# Gamebadge3_revB.net
KiCad netlist of a schematic drawn in EAGLE
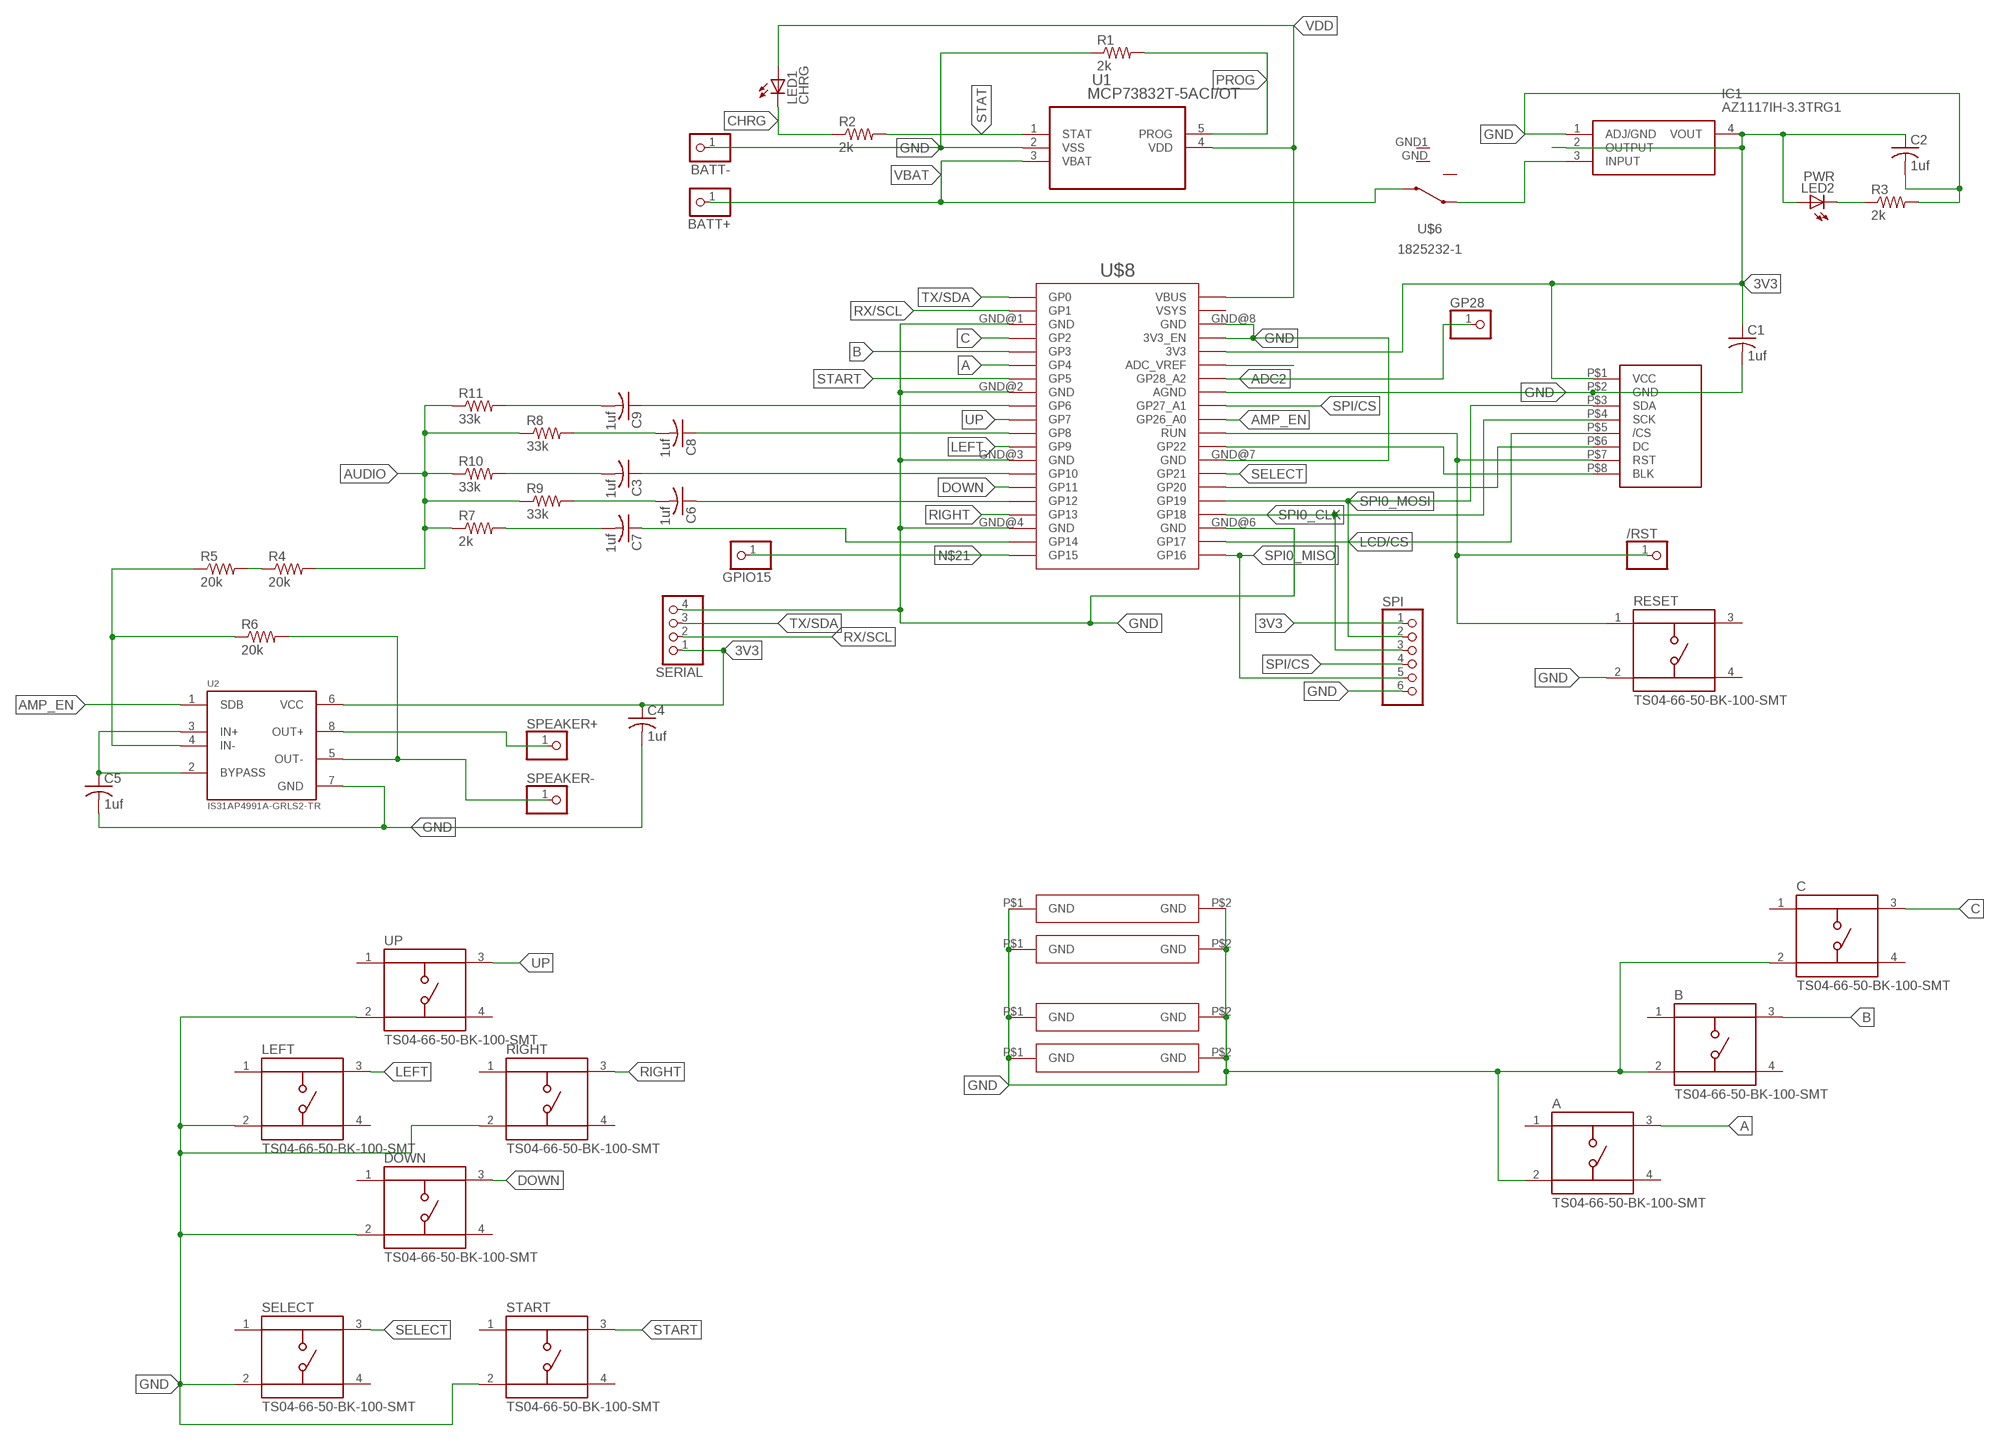
[diagram p0: schematic, sheet 1]

(export (version "E")
  (design (tool "Eeschema 10.0.6"))
  (components
    (comp (ref "/RST")
      (value "PINHD-1X1")
      (footprint "eagle-import:1X01")
      (libsource (lib "eagle-import") (part "PINHD-1X1"))
    )
    (comp (ref "A")
      (value "TS04-66-50-BK-100-SMT")
      (footprint "eagle-import:SW_TS04-66-50-BK-100-SMT")
      (fields (field (name "MF") "CUI Devices"))
      (libsource (lib "eagle-import") (part "TS04-66-50-BK-100-SMT"))
    )
    (comp (ref "B")
      (value "TS04-66-50-BK-100-SMT")
      (footprint "eagle-import:SW_TS04-66-50-BK-100-SMT")
      (fields (field (name "MF") "CUI Devices"))
      (libsource (lib "eagle-import") (part "TS04-66-50-BK-100-SMT"))
    )
    (comp (ref "BATT+")
      (value "PINHD-1X1")
      (footprint "eagle-import:1X01")
      (libsource (lib "eagle-import") (part "PINHD-1X1"))
    )
    (comp (ref "BATT-")
      (value "PINHD-1X1")
      (footprint "eagle-import:1X01")
      (libsource (lib "eagle-import") (part "PINHD-1X1"))
    )
    (comp (ref "C")
      (value "TS04-66-50-BK-100-SMT")
      (footprint "eagle-import:SW_TS04-66-50-BK-100-SMT")
      (fields (field (name "MF") "CUI Devices"))
      (libsource (lib "eagle-import") (part "TS04-66-50-BK-100-SMT"))
    )
    (comp (ref "C1")
      (value "1uf")
      (footprint "eagle-import:C0805")
      (libsource (lib "eagle-import") (part "C-USC0805"))
    )
    (comp (ref "C2")
      (value "1uf")
      (footprint "eagle-import:C0805")
      (libsource (lib "eagle-import") (part "C-USC0805"))
    )
    (comp (ref "C3")
      (value "1uf")
      (footprint "eagle-import:C0805")
      (libsource (lib "eagle-import") (part "C-USC0805"))
    )
    (comp (ref "C4")
      (value "1uf")
      (footprint "eagle-import:C0805")
      (libsource (lib "eagle-import") (part "C-USC0805"))
    )
    (comp (ref "C5")
      (value "1uf")
      (footprint "eagle-import:C0805")
      (libsource (lib "eagle-import") (part "C-USC0805"))
    )
    (comp (ref "C6")
      (value "1uf")
      (footprint "eagle-import:C0805")
      (libsource (lib "eagle-import") (part "C-USC0805"))
    )
    (comp (ref "C7")
      (value "1uf")
      (footprint "eagle-import:C0805")
      (libsource (lib "eagle-import") (part "C-USC0805"))
    )
    (comp (ref "C8")
      (value "1uf")
      (footprint "eagle-import:C0805")
      (libsource (lib "eagle-import") (part "C-USC0805"))
    )
    (comp (ref "C9")
      (value "1uf")
      (footprint "eagle-import:C0805")
      (libsource (lib "eagle-import") (part "C-USC0805"))
    )
    (comp (ref "DOWN")
      (value "TS04-66-50-BK-100-SMT")
      (footprint "eagle-import:SW_TS04-66-50-BK-100-SMT")
      (fields (field (name "MF") "CUI Devices"))
      (libsource (lib "eagle-import") (part "TS04-66-50-BK-100-SMT"))
    )
    (comp (ref "GP28")
      (value "PINHD-1X1")
      (footprint "eagle-import:1X01")
      (libsource (lib "eagle-import") (part "PINHD-1X1"))
    )
    (comp (ref "GPIO15")
      (value "PINHD-1X1")
      (footprint "eagle-import:1X01")
      (libsource (lib "eagle-import") (part "PINHD-1X1"))
    )
    (comp (ref "IC1")
      (value "AZ1117IH-3.3TRG1")
      (footprint "eagle-import:SOT230P700X170-4N")
      (fields (field (name "MF") "Diodes Inc."))
      (libsource (lib "eagle-import") (part "AZ1117IH-3.3TRG1"))
    )
    (comp (ref "LED1")
      (value "CHRG")
      (footprint "eagle-import:LED3MM")
      (libsource (lib "eagle-import") (part "LED3MM"))
    )
    (comp (ref "LED2")
      (value "PWR")
      (footprint "eagle-import:LED3MM")
      (libsource (lib "eagle-import") (part "LED3MM"))
    )
    (comp (ref "LEFT")
      (value "TS04-66-50-BK-100-SMT")
      (footprint "eagle-import:SW_TS04-66-50-BK-100-SMT")
      (fields (field (name "MF") "CUI Devices"))
      (libsource (lib "eagle-import") (part "TS04-66-50-BK-100-SMT"))
    )
    (comp (ref "R1")
      (value "2k")
      (footprint "eagle-import:R0805")
      (libsource (lib "eagle-import") (part "R-US_R0805"))
    )
    (comp (ref "R2")
      (value "2k")
      (footprint "eagle-import:R0805")
      (libsource (lib "eagle-import") (part "R-US_R0805"))
    )
    (comp (ref "R3")
      (value "2k")
      (footprint "eagle-import:R0805")
      (libsource (lib "eagle-import") (part "R-US_R0805"))
    )
    (comp (ref "R4")
      (value "20k")
      (footprint "eagle-import:R0805")
      (libsource (lib "eagle-import") (part "R-US_R0805"))
    )
    (comp (ref "R5")
      (value "20k")
      (footprint "eagle-import:R0805")
      (libsource (lib "eagle-import") (part "R-US_R0805"))
    )
    (comp (ref "R6")
      (value "20k")
      (footprint "eagle-import:R0805")
      (libsource (lib "eagle-import") (part "R-US_R0805"))
    )
    (comp (ref "R7")
      (value "2k")
      (footprint "eagle-import:R0805")
      (libsource (lib "eagle-import") (part "R-US_R0805"))
    )
    (comp (ref "R8")
      (value "33k")
      (footprint "eagle-import:R0805")
      (libsource (lib "eagle-import") (part "R-US_R0805"))
    )
    (comp (ref "R9")
      (value "33k")
      (footprint "eagle-import:R0805")
      (libsource (lib "eagle-import") (part "R-US_R0805"))
    )
    (comp (ref "R10")
      (value "33k")
      (footprint "eagle-import:R0805")
      (libsource (lib "eagle-import") (part "R-US_R0805"))
    )
    (comp (ref "R11")
      (value "33k")
      (footprint "eagle-import:R0805")
      (libsource (lib "eagle-import") (part "R-US_R0805"))
    )
    (comp (ref "RESET")
      (value "TS04-66-50-BK-100-SMT")
      (footprint "eagle-import:SW_TS04-66-50-BK-100-SMT")
      (fields (field (name "MF") "CUI Devices"))
      (libsource (lib "eagle-import") (part "TS04-66-50-BK-100-SMT"))
    )
    (comp (ref "RIGHT")
      (value "TS04-66-50-BK-100-SMT")
      (footprint "eagle-import:SW_TS04-66-50-BK-100-SMT")
      (fields (field (name "MF") "CUI Devices"))
      (libsource (lib "eagle-import") (part "TS04-66-50-BK-100-SMT"))
    )
    (comp (ref "SELECT")
      (value "TS04-66-50-BK-100-SMT")
      (footprint "eagle-import:SW_TS04-66-50-BK-100-SMT")
      (fields (field (name "MF") "CUI Devices"))
      (libsource (lib "eagle-import") (part "TS04-66-50-BK-100-SMT"))
    )
    (comp (ref "SERIAL")
      (value "PINHD-1X4")
      (footprint "eagle-import:1X04")
      (libsource (lib "eagle-import") (part "PINHD-1X4"))
    )
    (comp (ref "SPEAKER+")
      (value "PINHD-1X1")
      (footprint "eagle-import:1X01")
      (libsource (lib "eagle-import") (part "PINHD-1X1"))
    )
    (comp (ref "SPEAKER-")
      (value "PINHD-1X1")
      (footprint "eagle-import:1X01")
      (libsource (lib "eagle-import") (part "PINHD-1X1"))
    )
    (comp (ref "SPI")
      (value "PINHD-1X6")
      (footprint "eagle-import:1X06")
      (libsource (lib "eagle-import") (part "PINHD-1X6"))
    )
    (comp (ref "START")
      (value "TS04-66-50-BK-100-SMT")
      (footprint "eagle-import:SW_TS04-66-50-BK-100-SMT")
      (fields (field (name "MF") "CUI Devices"))
      (libsource (lib "eagle-import") (part "TS04-66-50-BK-100-SMT"))
    )
    (comp (ref "U$2")
      (value "GND_CLIP")
      (footprint "eagle-import:GND_CLIP")
      (libsource (lib "eagle-import") (part "GND_CLIP"))
    )
    (comp (ref "U$3")
      (value "GND_CLIP")
      (footprint "eagle-import:GND_CLIP")
      (libsource (lib "eagle-import") (part "GND_CLIP"))
    )
    (comp (ref "U$4")
      (value "GND_CLIP")
      (footprint "eagle-import:GND_CLIP")
      (libsource (lib "eagle-import") (part "GND_CLIP"))
    )
    (comp (ref "U$5")
      (value "GND_CLIP")
      (footprint "eagle-import:GND_CLIP")
      (libsource (lib "eagle-import") (part "GND_CLIP"))
    )
    (comp (ref "U$6")
      (value "1825232-1")
      (footprint "eagle-import:1825232-1")
      (fields (field (name "MF") "TE Connectivity"))
      (libsource (lib "eagle-import") (part "1825232-1"))
    )
    (comp (ref "U$7")
      (value "ST7789_CS")
      (footprint "eagle-import:ST7789_WAVE")
      (libsource (lib "eagle-import") (part "ST7789_CS"))
    )
    (comp (ref "U$8")
      (value "RPI_PICO_W")
      (footprint "eagle-import:RPI_PICO_W")
      (libsource (lib "eagle-import") (part "RPI_PICO_W"))
    )
    (comp (ref "U1")
      (value "MCP73832T-5ACI/OT")
      (footprint "eagle-import:SOT95P300X145-5N")
      (fields (field (name "MF") "Microchip"))
      (libsource (lib "eagle-import") (part "MCP73832T-5ACI/OT"))
    )
    (comp (ref "U2")
      (value "IS31AP4991A-GRLS2-TR")
      (footprint "eagle-import:SOIC127P604X170-8N")
      (fields (field (name "MF") "Lumissil Microsystems"))
      (libsource (lib "eagle-import") (part "IS31AP4991A-GRLS2-TR"))
    )
    (comp (ref "UP")
      (value "TS04-66-50-BK-100-SMT")
      (footprint "eagle-import:SW_TS04-66-50-BK-100-SMT")
      (fields (field (name "MF") "CUI Devices"))
      (libsource (lib "eagle-import") (part "TS04-66-50-BK-100-SMT"))
    )
  )
  (nets
    (net (code "1") (name "3V3") (class "Default")
      (node (ref "C1") (pin "1") (pinfunction "1_1") (pintype "passive"))
      (node (ref "C2") (pin "1") (pinfunction "1_1") (pintype "passive"))
      (node (ref "C4") (pin "1") (pinfunction "1_1") (pintype "passive"))
      (node (ref "IC1") (pin "2") (pinfunction "OUTPUT_2") (pintype "bidirectional"))
      (node (ref "IC1") (pin "4") (pinfunction "VOUT_4") (pintype "bidirectional"))
      (node (ref "LED2") (pin "A") (pinfunction "A_A") (pintype "passive"))
      (node (ref "SERIAL") (pin "1") (pinfunction "1_1") (pintype "passive"))
      (node (ref "SPI") (pin "1") (pinfunction "1_1") (pintype "passive"))
      (node (ref "U$7") (pin "P$1") (pinfunction "VCC_P$1") (pintype "bidirectional"))
      (node (ref "U$8") (pin "3V3") (pinfunction "3V3_3V3") (pintype "bidirectional"))
      (node (ref "U2") (pin "6") (pinfunction "VCC_6") (pintype "power_in"))
    )
    (net (code "2") (name "A") (class "Default")
      (node (ref "A") (pin "3") (pinfunction "3_3") (pintype "passive"))
      (node (ref "U$8") (pin "GP4") (pinfunction "GP4_GP4") (pintype "bidirectional"))
    )
    (net (code "3") (name "ADC2") (class "Default")
      (node (ref "GP28") (pin "1") (pinfunction "1_1") (pintype "passive"))
      (node (ref "U$8") (pin "GP28_A2") (pinfunction "GP28_A2_GP28_A2") (pintype "bidirectional"))
    )
    (net (code "4") (name "AMP_EN") (class "Default")
      (node (ref "U$8") (pin "GP26_A0") (pinfunction "GP26_A0_GP26_A0") (pintype "bidirectional"))
      (node (ref "U2") (pin "1") (pinfunction "SDB_1") (pintype "input"))
    )
    (net (code "5") (name "AUDIO") (class "Default")
      (node (ref "R10") (pin "1") (pinfunction "1_1") (pintype "passive"))
      (node (ref "R11") (pin "1") (pinfunction "1_1") (pintype "passive"))
      (node (ref "R4") (pin "2") (pinfunction "2_2") (pintype "passive"))
      (node (ref "R7") (pin "1") (pinfunction "1_1") (pintype "passive"))
      (node (ref "R8") (pin "1") (pinfunction "1_1") (pintype "passive"))
      (node (ref "R9") (pin "1") (pinfunction "1_1") (pintype "passive"))
    )
    (net (code "6") (name "B") (class "Default")
      (node (ref "B") (pin "3") (pinfunction "3_3") (pintype "passive"))
      (node (ref "U$8") (pin "GP3") (pinfunction "GP3_GP3") (pintype "bidirectional"))
    )
    (net (code "7") (name "C") (class "Default")
      (node (ref "C") (pin "3") (pinfunction "3_3") (pintype "passive"))
      (node (ref "U$8") (pin "GP2") (pinfunction "GP2_GP2") (pintype "bidirectional"))
    )
    (net (code "8") (name "CHRG") (class "Default")
      (node (ref "LED1") (pin "K") (pinfunction "C_K") (pintype "passive"))
      (node (ref "R2") (pin "1") (pinfunction "1_1") (pintype "passive"))
    )
    (net (code "9") (name "DOWN") (class "Default")
      (node (ref "DOWN") (pin "3") (pinfunction "3_3") (pintype "passive"))
      (node (ref "U$8") (pin "GP11") (pinfunction "GP11_GP11") (pintype "bidirectional"))
    )
    (net (code "10") (name "GND") (class "Default")
      (node (ref "A") (pin "2") (pinfunction "2_2") (pintype "passive"))
      (node (ref "B") (pin "2") (pinfunction "2_2") (pintype "passive"))
      (node (ref "BATT-") (pin "1") (pinfunction "1_1") (pintype "passive"))
      (node (ref "C") (pin "2") (pinfunction "2_2") (pintype "passive"))
      (node (ref "C1") (pin "2") (pinfunction "2_2") (pintype "passive"))
      (node (ref "C2") (pin "2") (pinfunction "2_2") (pintype "passive"))
      (node (ref "C4") (pin "2") (pinfunction "2_2") (pintype "passive"))
      (node (ref "C5") (pin "2") (pinfunction "2_2") (pintype "passive"))
      (node (ref "DOWN") (pin "2") (pinfunction "2_2") (pintype "passive"))
      (node (ref "IC1") (pin "1") (pinfunction "ADJ/GND_1") (pintype "bidirectional"))
      (node (ref "LEFT") (pin "2") (pinfunction "2_2") (pintype "passive"))
      (node (ref "R1") (pin "1") (pinfunction "1_1") (pintype "passive"))
      (node (ref "R3") (pin "2") (pinfunction "2_2") (pintype "passive"))
      (node (ref "RESET") (pin "2") (pinfunction "2_2") (pintype "passive"))
      (node (ref "RIGHT") (pin "2") (pinfunction "2_2") (pintype "passive"))
      (node (ref "SELECT") (pin "2") (pinfunction "2_2") (pintype "passive"))
      (node (ref "SERIAL") (pin "4") (pinfunction "4_4") (pintype "passive"))
      (node (ref "SPI") (pin "6") (pinfunction "6_6") (pintype "passive"))
      (node (ref "START") (pin "2") (pinfunction "2_2") (pintype "passive"))
      (node (ref "U$2") (pin "P$1") (pinfunction "GND_P$1") (pintype "bidirectional"))
      (node (ref "U$2") (pin "P$2") (pinfunction "GND_P$2") (pintype "bidirectional"))
      (node (ref "U$3") (pin "P$1") (pinfunction "GND_P$1") (pintype "bidirectional"))
      (node (ref "U$3") (pin "P$2") (pinfunction "GND_P$2") (pintype "bidirectional"))
      (node (ref "U$4") (pin "P$1") (pinfunction "GND_P$1") (pintype "bidirectional"))
      (node (ref "U$4") (pin "P$2") (pinfunction "GND_P$2") (pintype "bidirectional"))
      (node (ref "U$5") (pin "P$1") (pinfunction "GND_P$1") (pintype "bidirectional"))
      (node (ref "U$5") (pin "P$2") (pinfunction "GND_P$2") (pintype "bidirectional"))
      (node (ref "U$7") (pin "P$2") (pinfunction "GND_P$2") (pintype "bidirectional"))
      (node (ref "U$8") (pin "3V3_EN") (pinfunction "3V3_EN_3V3_EN") (pintype "bidirectional"))
      (node (ref "U$8") (pin "AGND") (pinfunction "AGND_AGND") (pintype "bidirectional"))
      (node (ref "U$8") (pin "GND@1") (pinfunction "GND_GND@1") (pintype "bidirectional"))
      (node (ref "U$8") (pin "GND@2") (pinfunction "GND_GND@2") (pintype "bidirectional"))
      (node (ref "U$8") (pin "GND@3") (pinfunction "GND_GND@3") (pintype "bidirectional"))
      (node (ref "U$8") (pin "GND@4") (pinfunction "GND_GND@4") (pintype "bidirectional"))
      (node (ref "U$8") (pin "GND@6") (pinfunction "GND_GND@6") (pintype "bidirectional"))
      (node (ref "U$8") (pin "GND@7") (pinfunction "GND_GND@7") (pintype "bidirectional"))
      (node (ref "U$8") (pin "GND@8") (pinfunction "GND_GND@8") (pintype "bidirectional"))
      (node (ref "U1") (pin "2") (pinfunction "VSS_2") (pintype "passive"))
      (node (ref "U2") (pin "7") (pinfunction "GND_7") (pintype "power_in"))
      (node (ref "UP") (pin "2") (pinfunction "2_2") (pintype "passive"))
    )
    (net (code "11") (name "LCD{slash}CS") (class "Default")
      (node (ref "U$7") (pin "P$5") (pinfunction "/CS_P$5") (pintype "bidirectional"))
      (node (ref "U$8") (pin "GP17") (pinfunction "GP17_GP17") (pintype "bidirectional"))
    )
    (net (code "12") (name "LEFT") (class "Default")
      (node (ref "LEFT") (pin "3") (pinfunction "3_3") (pintype "passive"))
      (node (ref "U$8") (pin "GP9") (pinfunction "GP9_GP9") (pintype "bidirectional"))
    )
    (net (code "13") (name "N$21") (class "Default")
      (node (ref "GPIO15") (pin "1") (pinfunction "1_1") (pintype "passive"))
      (node (ref "U$8") (pin "GP15") (pinfunction "GP15_GP15") (pintype "bidirectional"))
    )
    (net (code "14") (name "Net-(C3-Pad1)") (class "Default")
      (node (ref "C3") (pin "1") (pinfunction "1_1") (pintype "passive"))
      (node (ref "U$8") (pin "GP10") (pinfunction "GP10_GP10") (pintype "bidirectional"))
    )
    (net (code "15") (name "Net-(C3-Pad2)") (class "Default")
      (node (ref "C3") (pin "2") (pinfunction "2_2") (pintype "passive"))
      (node (ref "R10") (pin "2") (pinfunction "2_2") (pintype "passive"))
    )
    (net (code "16") (name "Net-(C6-Pad1)") (class "Default")
      (node (ref "C6") (pin "1") (pinfunction "1_1") (pintype "passive"))
      (node (ref "U$8") (pin "GP12") (pinfunction "GP12_GP12") (pintype "bidirectional"))
    )
    (net (code "17") (name "Net-(C6-Pad2)") (class "Default")
      (node (ref "C6") (pin "2") (pinfunction "2_2") (pintype "passive"))
      (node (ref "R9") (pin "2") (pinfunction "2_2") (pintype "passive"))
    )
    (net (code "18") (name "Net-(C7-Pad1)") (class "Default")
      (node (ref "C7") (pin "1") (pinfunction "1_1") (pintype "passive"))
      (node (ref "U$8") (pin "GP14") (pinfunction "GP14_GP14") (pintype "bidirectional"))
    )
    (net (code "19") (name "Net-(C7-Pad2)") (class "Default")
      (node (ref "C7") (pin "2") (pinfunction "2_2") (pintype "passive"))
      (node (ref "R7") (pin "2") (pinfunction "2_2") (pintype "passive"))
    )
    (net (code "20") (name "Net-(C8-Pad1)") (class "Default")
      (node (ref "C8") (pin "1") (pinfunction "1_1") (pintype "passive"))
      (node (ref "U$8") (pin "GP8") (pinfunction "GP8_GP8") (pintype "bidirectional"))
    )
    (net (code "21") (name "Net-(C8-Pad2)") (class "Default")
      (node (ref "C8") (pin "2") (pinfunction "2_2") (pintype "passive"))
      (node (ref "R8") (pin "2") (pinfunction "2_2") (pintype "passive"))
    )
    (net (code "22") (name "Net-(C9-Pad1)") (class "Default")
      (node (ref "C9") (pin "1") (pinfunction "1_1") (pintype "passive"))
      (node (ref "U$8") (pin "GP6") (pinfunction "GP6_GP6") (pintype "bidirectional"))
    )
    (net (code "23") (name "Net-(C9-Pad2)") (class "Default")
      (node (ref "C9") (pin "2") (pinfunction "2_2") (pintype "passive"))
      (node (ref "R11") (pin "2") (pinfunction "2_2") (pintype "passive"))
    )
    (net (code "24") (name "Net-(IC1-INPUT)") (class "Default")
      (node (ref "IC1") (pin "3") (pinfunction "INPUT_3") (pintype "bidirectional"))
      (node (ref "U$6") (pin "3") (pinfunction "3_3") (pintype "passive"))
    )
    (net (code "25") (name "Net-(LED2-C)") (class "Default")
      (node (ref "LED2") (pin "K") (pinfunction "C_K") (pintype "passive"))
      (node (ref "R3") (pin "1") (pinfunction "1_1") (pintype "passive"))
    )
    (net (code "26") (name "Net-(R4-Pad1)") (class "Default")
      (node (ref "R4") (pin "1") (pinfunction "1_1") (pintype "passive"))
      (node (ref "R5") (pin "2") (pinfunction "2_2") (pintype "passive"))
    )
    (net (code "27") (name "Net-(U$7-BLK)") (class "Default")
      (node (ref "U$7") (pin "P$8") (pinfunction "BLK_P$8") (pintype "bidirectional"))
      (node (ref "U$8") (pin "GP22") (pinfunction "GP22_GP22") (pintype "bidirectional"))
    )
    (net (code "28") (name "Net-(U$7-DC)") (class "Default")
      (node (ref "U$7") (pin "P$6") (pinfunction "DC_P$6") (pintype "bidirectional"))
      (node (ref "U$8") (pin "GP20") (pinfunction "GP20_GP20") (pintype "bidirectional"))
    )
    (net (code "29") (name "Net-(U$7-RST)") (class "Default")
      (node (ref "/RST") (pin "1") (pinfunction "1_1") (pintype "passive"))
      (node (ref "RESET") (pin "1") (pinfunction "1_1") (pintype "passive"))
      (node (ref "U$7") (pin "P$7") (pinfunction "RST_P$7") (pintype "bidirectional"))
      (node (ref "U$8") (pin "RUN") (pinfunction "RUN_RUN") (pintype "bidirectional"))
    )
    (net (code "30") (name "Net-(U2-BYPASS)") (class "Default")
      (node (ref "C5") (pin "1") (pinfunction "1_1") (pintype "passive"))
      (node (ref "U2") (pin "2") (pinfunction "BYPASS_2") (pintype "passive"))
      (node (ref "U2") (pin "3") (pinfunction "IN+_3") (pintype "input"))
    )
    (net (code "31") (name "Net-(U2-IN-)") (class "Default")
      (node (ref "R5") (pin "1") (pinfunction "1_1") (pintype "passive"))
      (node (ref "R6") (pin "1") (pinfunction "1_1") (pintype "passive"))
      (node (ref "U2") (pin "4") (pinfunction "IN-_4") (pintype "input"))
    )
    (net (code "32") (name "Net-(U2-OUT+)") (class "Default")
      (node (ref "SPEAKER+") (pin "1") (pinfunction "1_1") (pintype "passive"))
      (node (ref "U2") (pin "8") (pinfunction "OUT+_8") (pintype "output"))
    )
    (net (code "33") (name "Net-(U2-OUT-)") (class "Default")
      (node (ref "R6") (pin "2") (pinfunction "2_2") (pintype "passive"))
      (node (ref "SPEAKER-") (pin "1") (pinfunction "1_1") (pintype "passive"))
      (node (ref "U2") (pin "5") (pinfunction "OUT-_5") (pintype "output"))
    )
    (net (code "34") (name "PROG") (class "Default")
      (node (ref "R1") (pin "2") (pinfunction "2_2") (pintype "passive"))
      (node (ref "U1") (pin "5") (pinfunction "PROG_5") (pintype "input"))
    )
    (net (code "35") (name "RIGHT") (class "Default")
      (node (ref "RIGHT") (pin "3") (pinfunction "3_3") (pintype "passive"))
      (node (ref "U$8") (pin "GP13") (pinfunction "GP13_GP13") (pintype "bidirectional"))
    )
    (net (code "36") (name "RX{slash}SCL") (class "Default")
      (node (ref "SERIAL") (pin "2") (pinfunction "2_2") (pintype "passive"))
      (node (ref "U$8") (pin "GP1") (pinfunction "GP1_GP1") (pintype "bidirectional"))
    )
    (net (code "37") (name "SELECT") (class "Default")
      (node (ref "SELECT") (pin "3") (pinfunction "3_3") (pintype "passive"))
      (node (ref "U$8") (pin "GP21") (pinfunction "GP21_GP21") (pintype "bidirectional"))
    )
    (net (code "38") (name "SPI0_CLK") (class "Default")
      (node (ref "SPI") (pin "3") (pinfunction "3_3") (pintype "passive"))
      (node (ref "U$7") (pin "P$4") (pinfunction "SCK_P$4") (pintype "bidirectional"))
      (node (ref "U$8") (pin "GP18") (pinfunction "GP18_GP18") (pintype "bidirectional"))
    )
    (net (code "39") (name "SPI0_MISO") (class "Default")
      (node (ref "SPI") (pin "5") (pinfunction "5_5") (pintype "passive"))
      (node (ref "U$8") (pin "GP16") (pinfunction "GP16_GP16") (pintype "bidirectional"))
    )
    (net (code "40") (name "SPI0_MOSI") (class "Default")
      (node (ref "SPI") (pin "2") (pinfunction "2_2") (pintype "passive"))
      (node (ref "U$7") (pin "P$3") (pinfunction "SDA_P$3") (pintype "bidirectional"))
      (node (ref "U$8") (pin "GP19") (pinfunction "GP19_GP19") (pintype "bidirectional"))
    )
    (net (code "41") (name "SPI{slash}CS") (class "Default")
      (node (ref "SPI") (pin "4") (pinfunction "4_4") (pintype "passive"))
      (node (ref "U$8") (pin "GP27_A1") (pinfunction "GP27_A1_GP27_A1") (pintype "bidirectional"))
    )
    (net (code "42") (name "START") (class "Default")
      (node (ref "START") (pin "3") (pinfunction "3_3") (pintype "passive"))
      (node (ref "U$8") (pin "GP5") (pinfunction "GP5_GP5") (pintype "bidirectional"))
    )
    (net (code "43") (name "STAT") (class "Default")
      (node (ref "R2") (pin "2") (pinfunction "2_2") (pintype "passive"))
      (node (ref "U1") (pin "1") (pinfunction "STAT_1") (pintype "input"))
    )
    (net (code "44") (name "TX{slash}SDA") (class "Default")
      (node (ref "SERIAL") (pin "3") (pinfunction "3_3") (pintype "passive"))
      (node (ref "U$8") (pin "GP0") (pinfunction "GP0_GP0") (pintype "bidirectional"))
    )
    (net (code "45") (name "UP") (class "Default")
      (node (ref "U$8") (pin "GP7") (pinfunction "GP7_GP7") (pintype "bidirectional"))
      (node (ref "UP") (pin "3") (pinfunction "3_3") (pintype "passive"))
    )
    (net (code "46") (name "VBAT") (class "Default")
      (node (ref "BATT+") (pin "1") (pinfunction "1_1") (pintype "passive"))
      (node (ref "U$6") (pin "2") (pinfunction "2_2") (pintype "passive"))
      (node (ref "U1") (pin "3") (pinfunction "VBAT_3") (pintype "input"))
    )
    (net (code "47") (name "VDD") (class "Default")
      (node (ref "LED1") (pin "A") (pinfunction "A_A") (pintype "passive"))
      (node (ref "U$8") (pin "VBUS") (pinfunction "VBUS_VBUS") (pintype "bidirectional"))
      (node (ref "U1") (pin "4") (pinfunction "VDD_4") (pintype "power_in"))
    )
    (net (code "48") (name "unconnected-(A-Pad1)") (class "Default")
      (node (ref "A") (pin "1") (pinfunction "1_1") (pintype "passive"))
    )
    (net (code "49") (name "unconnected-(A-Pad4)") (class "Default")
      (node (ref "A") (pin "4") (pinfunction "4_4") (pintype "passive"))
    )
    (net (code "50") (name "unconnected-(B-Pad1)") (class "Default")
      (node (ref "B") (pin "1") (pinfunction "1_1") (pintype "passive"))
    )
    (net (code "51") (name "unconnected-(B-Pad4)") (class "Default")
      (node (ref "B") (pin "4") (pinfunction "4_4") (pintype "passive"))
    )
    (net (code "52") (name "unconnected-(C-Pad1)") (class "Default")
      (node (ref "C") (pin "1") (pinfunction "1_1") (pintype "passive"))
    )
    (net (code "53") (name "unconnected-(C-Pad4)") (class "Default")
      (node (ref "C") (pin "4") (pinfunction "4_4") (pintype "passive"))
    )
    (net (code "54") (name "unconnected-(DOWN-Pad1)") (class "Default")
      (node (ref "DOWN") (pin "1") (pinfunction "1_1") (pintype "passive"))
    )
    (net (code "55") (name "unconnected-(DOWN-Pad4)") (class "Default")
      (node (ref "DOWN") (pin "4") (pinfunction "4_4") (pintype "passive"))
    )
    (net (code "56") (name "unconnected-(LEFT-Pad1)") (class "Default")
      (node (ref "LEFT") (pin "1") (pinfunction "1_1") (pintype "passive"))
    )
    (net (code "57") (name "unconnected-(LEFT-Pad4)") (class "Default")
      (node (ref "LEFT") (pin "4") (pinfunction "4_4") (pintype "passive"))
    )
    (net (code "58") (name "unconnected-(RESET-Pad3)") (class "Default")
      (node (ref "RESET") (pin "3") (pinfunction "3_3") (pintype "passive"))
    )
    (net (code "59") (name "unconnected-(RESET-Pad4)") (class "Default")
      (node (ref "RESET") (pin "4") (pinfunction "4_4") (pintype "passive"))
    )
    (net (code "60") (name "unconnected-(RIGHT-Pad1)") (class "Default")
      (node (ref "RIGHT") (pin "1") (pinfunction "1_1") (pintype "passive"))
    )
    (net (code "61") (name "unconnected-(RIGHT-Pad4)") (class "Default")
      (node (ref "RIGHT") (pin "4") (pinfunction "4_4") (pintype "passive"))
    )
    (net (code "62") (name "unconnected-(SELECT-Pad1)") (class "Default")
      (node (ref "SELECT") (pin "1") (pinfunction "1_1") (pintype "passive"))
    )
    (net (code "63") (name "unconnected-(SELECT-Pad4)") (class "Default")
      (node (ref "SELECT") (pin "4") (pinfunction "4_4") (pintype "passive"))
    )
    (net (code "64") (name "unconnected-(START-Pad1)") (class "Default")
      (node (ref "START") (pin "1") (pinfunction "1_1") (pintype "passive"))
    )
    (net (code "65") (name "unconnected-(START-Pad4)") (class "Default")
      (node (ref "START") (pin "4") (pinfunction "4_4") (pintype "passive"))
    )
    (net (code "66") (name "unconnected-(U$6-Pad1)") (class "Default")
      (node (ref "U$6") (pin "1") (pinfunction "1_1") (pintype "passive"))
    )
    (net (code "67") (name "unconnected-(U$6-PadGND)") (class "Default")
      (node (ref "U$6") (pin "GND") (pinfunction "GND_GND") (pintype "passive"))
    )
    (net (code "68") (name "unconnected-(U$6-PadGND1)") (class "Default")
      (node (ref "U$6") (pin "GND1") (pinfunction "GND1_GND1") (pintype "passive"))
    )
    (net (code "69") (name "unconnected-(U$8-PadADC_VREF)") (class "Default")
      (node (ref "U$8") (pin "ADC_VREF") (pinfunction "ADC_VREF_ADC_VREF") (pintype "bidirectional"))
    )
    (net (code "70") (name "unconnected-(U$8-PadVSYS)") (class "Default")
      (node (ref "U$8") (pin "VSYS") (pinfunction "VSYS_VSYS") (pintype "bidirectional"))
    )
    (net (code "71") (name "unconnected-(UP-Pad1)") (class "Default")
      (node (ref "UP") (pin "1") (pinfunction "1_1") (pintype "passive"))
    )
    (net (code "72") (name "unconnected-(UP-Pad4)") (class "Default")
      (node (ref "UP") (pin "4") (pinfunction "4_4") (pintype "passive"))
    )
  )
)
